# LM2596.net
KiCad netlist of a schematic drawn in Altium Designer
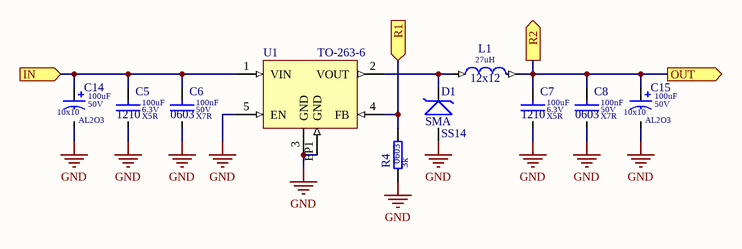
[diagram p0: LM2596.SchDoc]

(export (version "E")
  (design (tool "Eeschema 10.0.6"))
  (components
    (comp (ref "C5")
      (value "100uF")
      (footprint "C_1210_3225")
      (description "Capacitor")
      (fields
        (field (name "DIELECTRIC") "X5R")
        (field (name "VOLTAGE") "6.3V")
        (field (name "SCH_FOOTPRINT") "1210")
        (field (name "PART NUMBER") "C_100uF_6.3V_X5R_1210_20")
        (field (name "MANUFACTURER") "TDK")
      )
      (libsource (lib "Library") (part "C"))
    )
    (comp (ref "C6")
      (value "100nF")
      (footprint "C_0603_1608")
      (description "Capacitor")
      (fields
        (field (name "DIELECTRIC") "X7R")
        (field (name "VOLTAGE") "50V")
        (field (name "SCH_FOOTPRINT") "0603")
        (field (name "PART NUMBER") "C_100nF_50V_X7R_0603_5")
        (field (name "MANUFACTURER") "Samsung")
      )
      (libsource (lib "Library") (part "C"))
    )
    (comp (ref "C7")
      (value "100uF")
      (footprint "C_1210_3225")
      (description "Capacitor")
      (fields
        (field (name "DIELECTRIC") "X5R")
        (field (name "VOLTAGE") "6.3V")
        (field (name "SCH_FOOTPRINT") "1210")
        (field (name "PART NUMBER") "C_100uF_6.3V_X5R_1210_20")
        (field (name "MANUFACTURER") "TDK")
      )
      (libsource (lib "Library") (part "C"))
    )
    (comp (ref "C8")
      (value "100nF")
      (footprint "C_0603_1608")
      (description "Capacitor")
      (fields
        (field (name "DIELECTRIC") "X7R")
        (field (name "VOLTAGE") "50V")
        (field (name "SCH_FOOTPRINT") "0603")
        (field (name "PART NUMBER") "C_100nF_50V_X7R_0603_5")
        (field (name "MANUFACTURER") "Samsung")
      )
      (libsource (lib "Library") (part "C"))
    )
    (comp (ref "C14")
      (value "100uF")
      (footprint "CE_D_10x10MM")
      (description "Polarized Capacitor")
      (fields
        (field (name "DIELECTRIC") "AL2O3")
        (field (name "SCH_FOOTPRINT") "10x10")
        (field (name "VOLTAGE") "50V")
        (field (name "PART NUMBER") "CE_100uF_50V_AL2O3_10x10_20")
        (field (name "MANUFACTURER") "Nichicon")
      )
      (libsource (lib "Library") (part "CE"))
    )
    (comp (ref "C15")
      (value "100uF")
      (footprint "CE_D_10x10MM")
      (description "Polarized Capacitor")
      (fields
        (field (name "DIELECTRIC") "AL2O3")
        (field (name "SCH_FOOTPRINT") "10x10")
        (field (name "VOLTAGE") "50V")
        (field (name "PART NUMBER") "CE_100uF_50V_AL2O3_10x10_20")
        (field (name "MANUFACTURER") "Nichicon")
      )
      (libsource (lib "Library") (part "CE"))
    )
    (comp (ref "D1")
      (value "SS14")
      (footprint "SMA_DO-214AC")
      (fields
        (field (name "SCH_FOOTPRINT") "SMA")
        (field (name "PART NUMBER") "DS_SS14_1A_40V_SMA")
        (field (name "VOLTAGE") "40V")
        (field (name "MANUFACTURER") "Fairchild Semiconductor")
      )
      (libsource (lib "Library") (part "DS"))
    )
    (comp (ref "L1")
      (value "27uH")
      (footprint "L_SRR1280-XXXY")
      (description "Induction")
      (fields
        (field (name "SCH_FOOTPRINT") "12x12")
        (field (name "PART NUMBER") "L_27uH_3.9A_SRR1280")
        (field (name "MANUFACTURER") "Bourns")
      )
      (libsource (lib "Library") (part "L"))
    )
    (comp (ref "R4")
      (value "3k")
      (footprint "R_NC_0603_1608")
      (fields
        (field (name "SCH_FOOTPRINT") "0603")
        (field (name "PART NUMBER") "R_GENERIC_0603")
        (field (name "Comment") "Resistor")
      )
      (libsource (lib "Library") (part "R"))
    )
    (comp (ref "U1")
      (value "VR_LM2596")
      (footprint "TO-263-6")
      (fields (field (name "SCH_FOOTPRINT") "TO-263-6") (field (name "PART NUMBER") "VR_LM2596-ADJ"))
      (libsource (lib "Lib") (part "VR_LM2596"))
    )
  )
  (nets
    (net (code "1") (name "/IN") (class "Default")
      (node (ref "C14") (pin "1") (pinfunction "1_1") (pintype "passive"))
      (node (ref "C5") (pin "1") (pinfunction "1_1") (pintype "passive"))
      (node (ref "C6") (pin "1") (pinfunction "1_1") (pintype "passive"))
      (node (ref "U1") (pin "1") (pinfunction "VIN_1") (pintype "input"))
    )
    (net (code "2") (name "/OUT") (class "Default")
      (node (ref "C15") (pin "1") (pinfunction "1_1") (pintype "passive"))
      (node (ref "C7") (pin "1") (pinfunction "1_1") (pintype "passive"))
      (node (ref "C8") (pin "1") (pinfunction "1_1") (pintype "passive"))
      (node (ref "L1") (pin "2") (pinfunction "2_2") (pintype "output"))
    )
    (net (code "3") (name "/R1") (class "Default")
      (node (ref "R4") (pin "2") (pinfunction "2_2") (pintype "passive"))
      (node (ref "U1") (pin "4") (pinfunction "FB_4") (pintype "input"))
    )
    (net (code "4") (name "GND") (class "Default")
      (node (ref "C14") (pin "2") (pinfunction "2_2") (pintype "passive"))
      (node (ref "C15") (pin "2") (pinfunction "2_2") (pintype "passive"))
      (node (ref "C5") (pin "2") (pinfunction "2_2") (pintype "passive"))
      (node (ref "C6") (pin "2") (pinfunction "2_2") (pintype "passive"))
      (node (ref "C7") (pin "2") (pinfunction "2_2") (pintype "passive"))
      (node (ref "C8") (pin "2") (pinfunction "2_2") (pintype "passive"))
      (node (ref "D1") (pin "2") (pintype "passive"))
      (node (ref "R4") (pin "1") (pinfunction "1_1") (pintype "passive"))
      (node (ref "U1") (pin "3") (pinfunction "GND_3") (pintype "power_in"))
      (node (ref "U1") (pin "5") (pinfunction "EN_5") (pintype "input"))
      (node (ref "U1") (pin "EP1") (pinfunction "GND_EP1") (pintype "input"))
    )
    (net (code "5") (name "Net-(U1-VOUT)") (class "Default")
      (node (ref "D1") (pin "1") (pintype "passive"))
      (node (ref "L1") (pin "1") (pinfunction "1_1") (pintype "input"))
      (node (ref "U1") (pin "2") (pinfunction "VOUT_2") (pintype "output"))
    )
  )
)
